# base.net
KiCad netlist of a schematic drawn in EAGLE
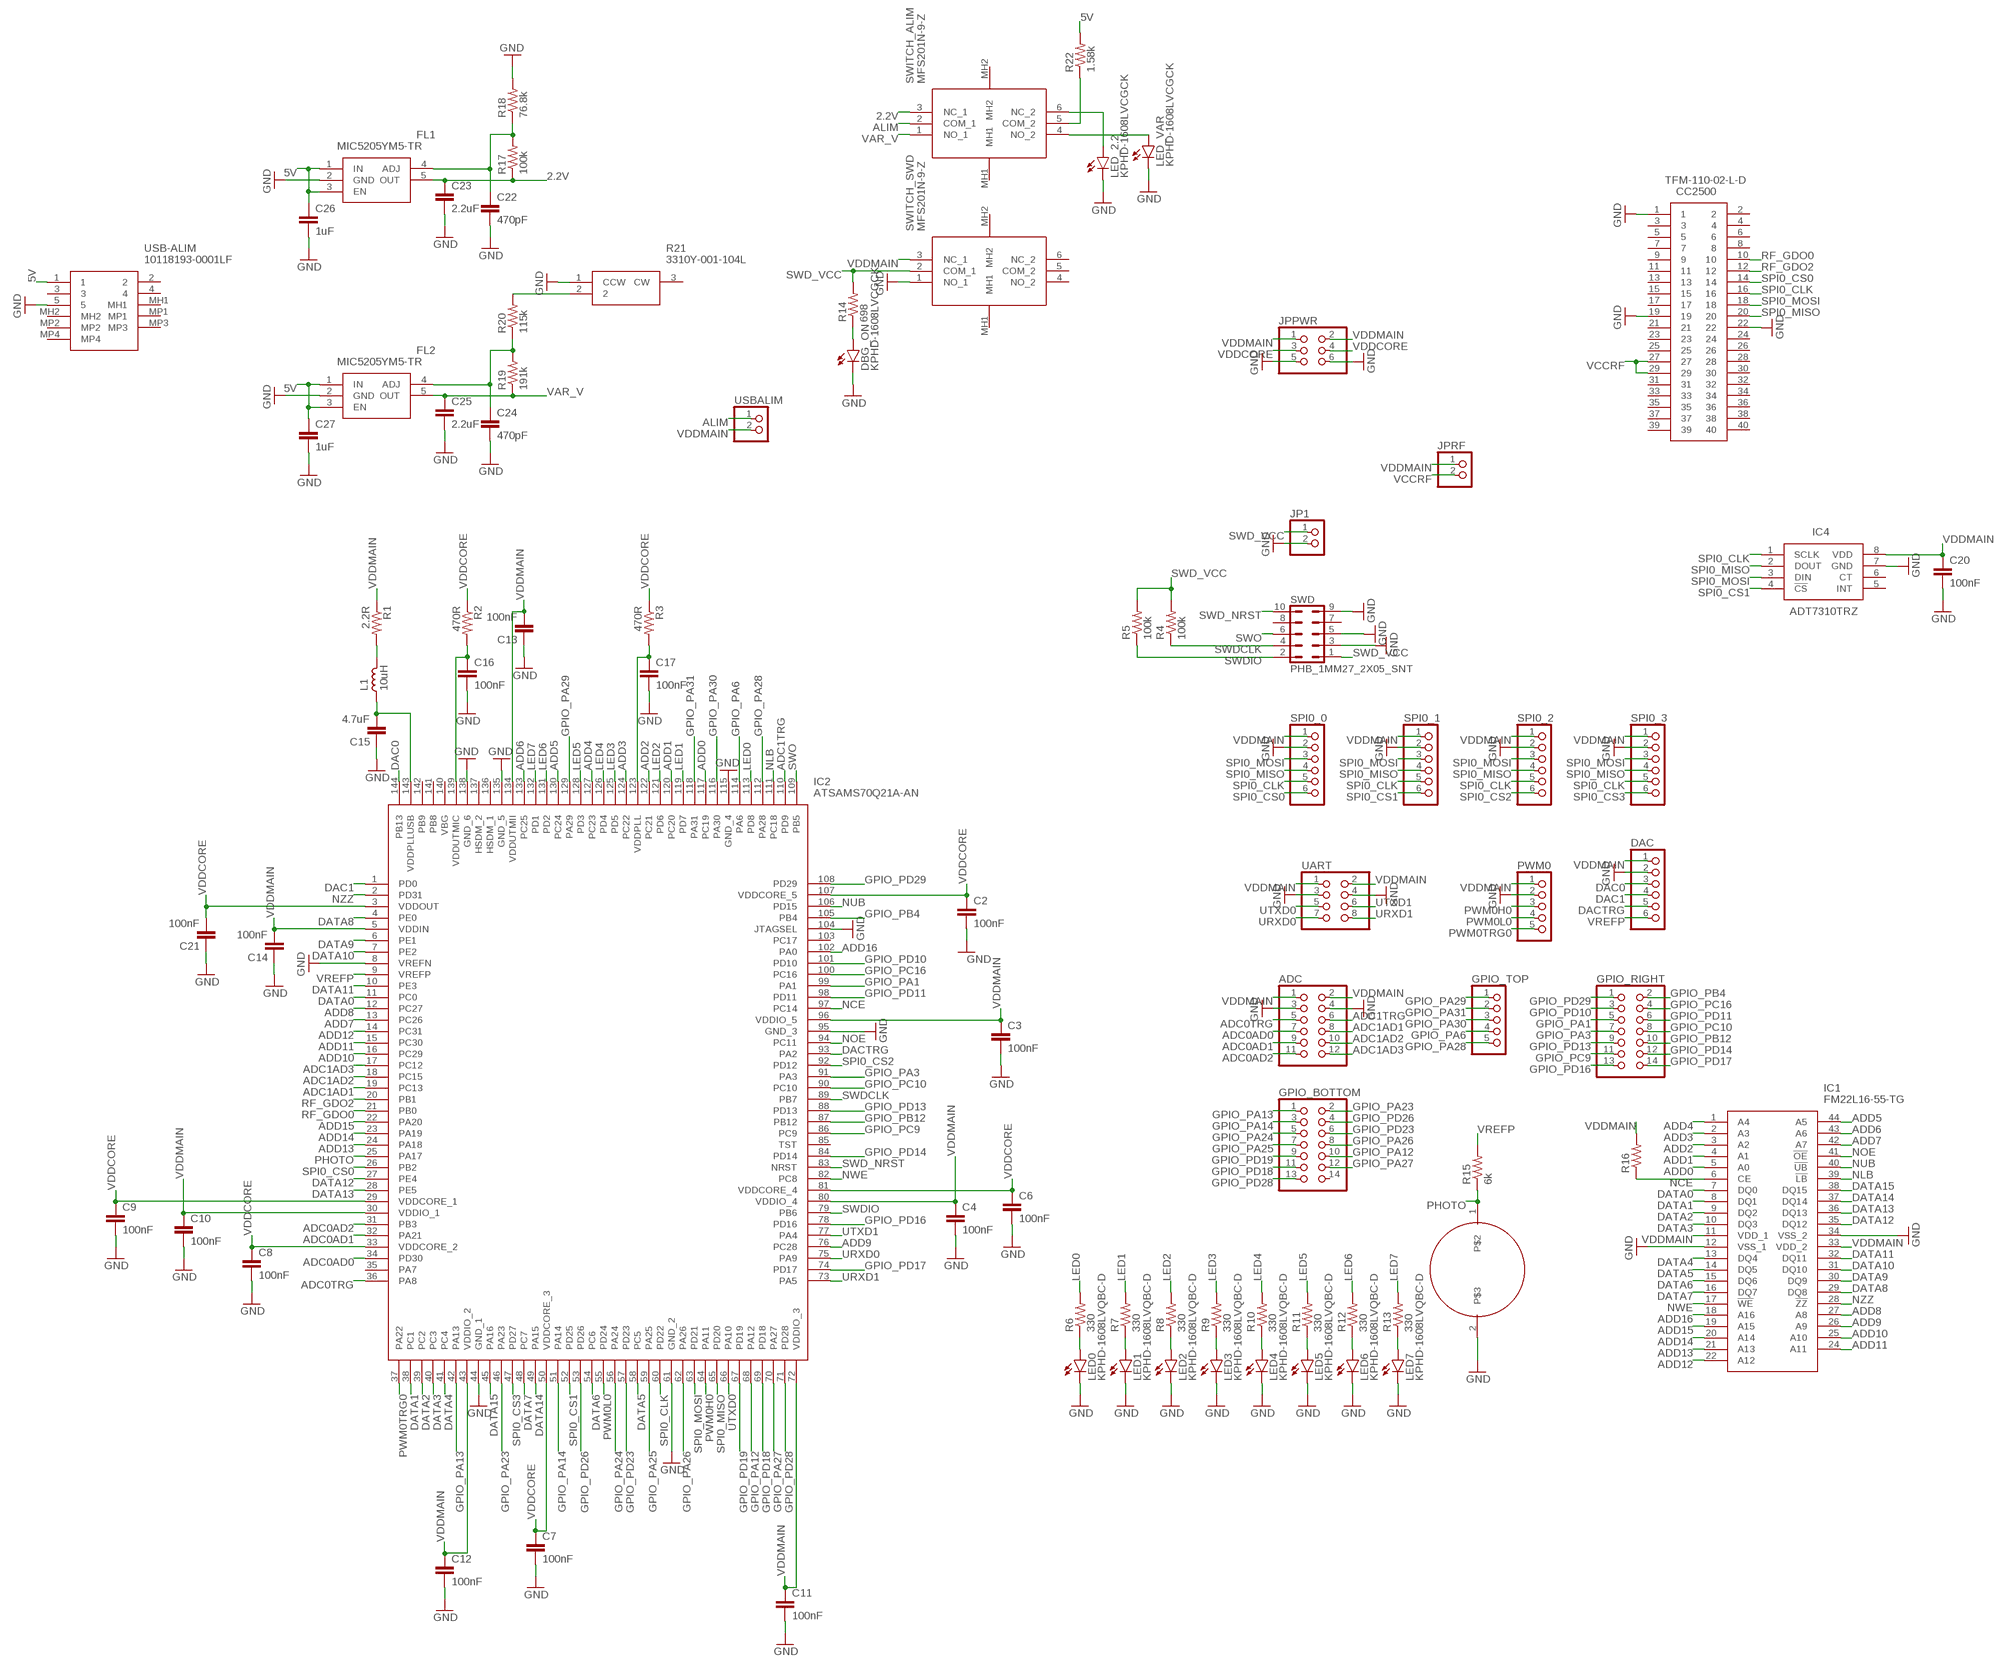
[diagram p0: schematic, sheet 1]

(export (version "E")
  (design (tool "Eeschema 10.0.6"))
  (components
    (comp (ref "ADC")
      (value "PINHD-2X6")
      (footprint "eagle-import:2X06")
      (libsource (lib "eagle-import") (part "PINHD-2X6"))
    )
    (comp (ref "C2")
      (value "100nF")
      (footprint "eagle-import:C0603")
      (libsource (lib "eagle-import") (part "C-EUC0603"))
    )
    (comp (ref "C3")
      (value "100nF")
      (footprint "eagle-import:C0603")
      (libsource (lib "eagle-import") (part "C-EUC0603"))
    )
    (comp (ref "C4")
      (value "100nF")
      (footprint "eagle-import:C0603")
      (libsource (lib "eagle-import") (part "C-EUC0603"))
    )
    (comp (ref "C6")
      (value "100nF")
      (footprint "eagle-import:C0603")
      (libsource (lib "eagle-import") (part "C-EUC0603"))
    )
    (comp (ref "C7")
      (value "100nF")
      (footprint "eagle-import:C0603")
      (libsource (lib "eagle-import") (part "C-EUC0603"))
    )
    (comp (ref "C8")
      (value "100nF")
      (footprint "eagle-import:C0603")
      (libsource (lib "eagle-import") (part "C-EUC0603"))
    )
    (comp (ref "C9")
      (value "100nF")
      (footprint "eagle-import:C0603")
      (libsource (lib "eagle-import") (part "C-EUC0603"))
    )
    (comp (ref "C10")
      (value "100nF")
      (footprint "eagle-import:C0603")
      (libsource (lib "eagle-import") (part "C-EUC0603"))
    )
    (comp (ref "C11")
      (value "100nF")
      (footprint "eagle-import:C0603")
      (libsource (lib "eagle-import") (part "C-EUC0603"))
    )
    (comp (ref "C12")
      (value "100nF")
      (footprint "eagle-import:C0603")
      (libsource (lib "eagle-import") (part "C-EUC0603"))
    )
    (comp (ref "C13")
      (value "100nF")
      (footprint "eagle-import:C0603")
      (libsource (lib "eagle-import") (part "C-EUC0603"))
    )
    (comp (ref "C14")
      (value "100nF")
      (footprint "eagle-import:C0603")
      (libsource (lib "eagle-import") (part "C-EUC0603"))
    )
    (comp (ref "C15")
      (value "4.7uF")
      (footprint "eagle-import:C0603")
      (libsource (lib "eagle-import") (part "C-EUC0603"))
    )
    (comp (ref "C16")
      (value "100nF")
      (footprint "eagle-import:C0603")
      (libsource (lib "eagle-import") (part "C-EUC0603"))
    )
    (comp (ref "C17")
      (value "100nF")
      (footprint "eagle-import:C0603")
      (libsource (lib "eagle-import") (part "C-EUC0603"))
    )
    (comp (ref "C20")
      (value "100nF")
      (footprint "eagle-import:C0603")
      (libsource (lib "eagle-import") (part "C-EUC0603"))
    )
    (comp (ref "C21")
      (value "100nF")
      (footprint "eagle-import:C0603")
      (libsource (lib "eagle-import") (part "C-EUC0603"))
    )
    (comp (ref "C22")
      (value "470pF")
      (footprint "eagle-import:C0603")
      (libsource (lib "eagle-import") (part "C-EUC0603"))
    )
    (comp (ref "C23")
      (value "2.2uF")
      (footprint "eagle-import:C0603")
      (libsource (lib "eagle-import") (part "C-EUC0603"))
    )
    (comp (ref "C24")
      (value "470pF")
      (footprint "eagle-import:C0603")
      (libsource (lib "eagle-import") (part "C-EUC0603"))
    )
    (comp (ref "C25")
      (value "2.2uF")
      (footprint "eagle-import:C0603")
      (libsource (lib "eagle-import") (part "C-EUC0603"))
    )
    (comp (ref "C26")
      (value "1uF")
      (footprint "eagle-import:C0603")
      (libsource (lib "eagle-import") (part "C-EUC0603"))
    )
    (comp (ref "C27")
      (value "1uF")
      (footprint "eagle-import:C0603")
      (libsource (lib "eagle-import") (part "C-EUC0603"))
    )
    (comp (ref "CC2500")
      (value "TFM-110-02-L-D")
      (footprint "eagle-import:TFM-110-02-L")
      (fields (field (name "MOUSER_PART_NUMBER") "200-TFM11002LD") (field (name "RS_PART_NUMBER") "7655947"))
      (libsource (lib "eagle-import") (part "TFM-110-02-L-D"))
    )
    (comp (ref "DAC")
      (value "PINHD-1X6")
      (footprint "eagle-import:1X06")
      (libsource (lib "eagle-import") (part "PINHD-1X6"))
    )
    (comp (ref "DBG_ON")
      (value "KPHD-1608LVCGCK")
      (footprint "eagle-import:CHIP-LED0603")
      (libsource (lib "eagle-import") (part "LEDCHIP-LED0603"))
    )
    (comp (ref "FL1")
      (value "MIC5205YM5-TR")
      (footprint "eagle-import:SOT95P280X145-5N")
      (fields
        (field (name "MOUSER_PART_NUMBER") "998-MIC5205YM5TR")
        (field (name "RS_PART_NUMBER") "9101449P")
      )
      (libsource (lib "eagle-import") (part "MIC5205YM5-TR"))
    )
    (comp (ref "FL2")
      (value "MIC5205YM5-TR")
      (footprint "eagle-import:SOT95P280X145-5N")
      (fields
        (field (name "MOUSER_PART_NUMBER") "998-MIC5205YM5TR")
        (field (name "RS_PART_NUMBER") "9101449P")
      )
      (libsource (lib "eagle-import") (part "MIC5205YM5-TR"))
    )
    (comp (ref "GPIO_BOTTOM")
      (value "PINHD-2X7")
      (footprint "eagle-import:2X07")
      (libsource (lib "eagle-import") (part "PINHD-2X7"))
    )
    (comp (ref "GPIO_RIGHT")
      (value "PINHD-2X7")
      (footprint "eagle-import:2X07")
      (libsource (lib "eagle-import") (part "PINHD-2X7"))
    )
    (comp (ref "GPIO_TOP")
      (value "PINHD-1X5")
      (footprint "eagle-import:1X05")
      (libsource (lib "eagle-import") (part "PINHD-1X5"))
    )
    (comp (ref "IC1")
      (value "FM22L16-55-TG")
      (footprint "eagle-import:SOP80P1184X119-44N")
      (fields
        (field (name "MOUSER_PART_NUMBER") "877-FM22L16-55-TG")
        (field (name "RS_PART_NUMBER") "1254206P")
      )
      (libsource (lib "eagle-import") (part "FM22L16-55-TG"))
    )
    (comp (ref "IC2")
      (value "ATSAMS70Q21A-AN")
      (footprint "eagle-import:QFP50P2200X2200X160-144N")
      (fields
        (field (name "MOUSER_PART_NUMBER") "556-ATSAMS70Q21A-AN")
        (field (name "RS_PART_NUMBER") "1773760P")
      )
      (libsource (lib "eagle-import") (part "ATSAMS70Q21A-AN"))
    )
    (comp (ref "IC4")
      (value "ADT7310TRZ")
      (footprint "eagle-import:SOIC127P600X175-8N")
      (fields (field (name "MOUSER_PART_NUMBER") "584-ADT7310TRZ") (field (name "RS_PART_NUMBER") "7969022P"))
      (libsource (lib "eagle-import") (part "ADT7310TRZ"))
    )
    (comp (ref "JP1")
      (value "PINHD-1X2")
      (footprint "eagle-import:1X02")
      (libsource (lib "eagle-import") (part "PINHD-1X2"))
    )
    (comp (ref "JPPWR")
      (value "PINHD-2X3")
      (footprint "eagle-import:2X03")
      (libsource (lib "eagle-import") (part "PINHD-2X3"))
    )
    (comp (ref "JPRF")
      (value "PINHD-1X2")
      (footprint "eagle-import:1X02")
      (libsource (lib "eagle-import") (part "PINHD-1X2"))
    )
    (comp (ref "L1")
      (value "10uH")
      (footprint "eagle-import:L0603")
      (libsource (lib "eagle-import") (part "L_0603"))
    )
    (comp (ref "LED0")
      (value "KPHD-1608LVQBC-D")
      (footprint "eagle-import:CHIP-LED0603")
      (libsource (lib "eagle-import") (part "LEDCHIP-LED0603"))
    )
    (comp (ref "LED1")
      (value "KPHD-1608LVQBC-D")
      (footprint "eagle-import:CHIP-LED0603")
      (libsource (lib "eagle-import") (part "LEDCHIP-LED0603"))
    )
    (comp (ref "LED2")
      (value "KPHD-1608LVQBC-D")
      (footprint "eagle-import:CHIP-LED0603")
      (libsource (lib "eagle-import") (part "LEDCHIP-LED0603"))
    )
    (comp (ref "LED3")
      (value "KPHD-1608LVQBC-D")
      (footprint "eagle-import:CHIP-LED0603")
      (libsource (lib "eagle-import") (part "LEDCHIP-LED0603"))
    )
    (comp (ref "LED4")
      (value "KPHD-1608LVQBC-D")
      (footprint "eagle-import:CHIP-LED0603")
      (libsource (lib "eagle-import") (part "LEDCHIP-LED0603"))
    )
    (comp (ref "LED5")
      (value "KPHD-1608LVQBC-D")
      (footprint "eagle-import:CHIP-LED0603")
      (libsource (lib "eagle-import") (part "LEDCHIP-LED0603"))
    )
    (comp (ref "LED6")
      (value "KPHD-1608LVQBC-D")
      (footprint "eagle-import:CHIP-LED0603")
      (libsource (lib "eagle-import") (part "LEDCHIP-LED0603"))
    )
    (comp (ref "LED7")
      (value "KPHD-1608LVQBC-D")
      (footprint "eagle-import:CHIP-LED0603")
      (libsource (lib "eagle-import") (part "LEDCHIP-LED0603"))
    )
    (comp (ref "LED_2.2")
      (value "KPHD-1608LVCGCK")
      (footprint "eagle-import:CHIP-LED0603")
      (libsource (lib "eagle-import") (part "LEDCHIP-LED0603"))
    )
    (comp (ref "LED_VAR")
      (value "KPHD-1608LVCGCK")
      (footprint "eagle-import:CHIP-LED0603")
      (libsource (lib "eagle-import") (part "LEDCHIP-LED0603"))
    )
    (comp (ref "PWM0")
      (value "PINHD-1X5")
      (footprint "eagle-import:1X05")
      (libsource (lib "eagle-import") (part "PINHD-1X5"))
    )
    (comp (ref "R1")
      (value "2.2R")
      (footprint "eagle-import:R0603")
      (libsource (lib "eagle-import") (part "R-US_R0603"))
    )
    (comp (ref "R2")
      (value "470R")
      (footprint "eagle-import:R0603")
      (libsource (lib "eagle-import") (part "R-US_R0603"))
    )
    (comp (ref "R3")
      (value "470R")
      (footprint "eagle-import:R0603")
      (libsource (lib "eagle-import") (part "R-US_R0603"))
    )
    (comp (ref "R4")
      (value "100k")
      (footprint "eagle-import:R0603")
      (libsource (lib "eagle-import") (part "R-US_R0603"))
    )
    (comp (ref "R5")
      (value "100k")
      (footprint "eagle-import:R0603")
      (libsource (lib "eagle-import") (part "R-US_R0603"))
    )
    (comp (ref "R6")
      (value "330")
      (footprint "eagle-import:R0603")
      (libsource (lib "eagle-import") (part "R-US_R0603"))
    )
    (comp (ref "R7")
      (value "330")
      (footprint "eagle-import:R0603")
      (libsource (lib "eagle-import") (part "R-US_R0603"))
    )
    (comp (ref "R8")
      (value "330")
      (footprint "eagle-import:R0603")
      (libsource (lib "eagle-import") (part "R-US_R0603"))
    )
    (comp (ref "R9")
      (value "330")
      (footprint "eagle-import:R0603")
      (libsource (lib "eagle-import") (part "R-US_R0603"))
    )
    (comp (ref "R10")
      (value "330")
      (footprint "eagle-import:R0603")
      (libsource (lib "eagle-import") (part "R-US_R0603"))
    )
    (comp (ref "R11")
      (value "330")
      (footprint "eagle-import:R0603")
      (libsource (lib "eagle-import") (part "R-US_R0603"))
    )
    (comp (ref "R12")
      (value "330")
      (footprint "eagle-import:R0603")
      (libsource (lib "eagle-import") (part "R-US_R0603"))
    )
    (comp (ref "R13")
      (value "330")
      (footprint "eagle-import:R0603")
      (libsource (lib "eagle-import") (part "R-US_R0603"))
    )
    (comp (ref "R14")
      (value "698")
      (footprint "eagle-import:R0603")
      (libsource (lib "eagle-import") (part "R-US_R0603"))
    )
    (comp (ref "R15")
      (value "6k")
      (footprint "eagle-import:R0603")
      (libsource (lib "eagle-import") (part "R-US_R0603"))
    )
    (comp (ref "R16")
      (value "R-US_R0603")
      (footprint "eagle-import:R0603")
      (libsource (lib "eagle-import") (part "R-US_R0603"))
    )
    (comp (ref "R17")
      (value "100k")
      (footprint "eagle-import:R0603")
      (libsource (lib "eagle-import") (part "R-US_R0603"))
    )
    (comp (ref "R18")
      (value "76.8k")
      (footprint "eagle-import:R0603")
      (libsource (lib "eagle-import") (part "R-US_R0603"))
    )
    (comp (ref "R19")
      (value "191k")
      (footprint "eagle-import:R0603")
      (libsource (lib "eagle-import") (part "R-US_R0603"))
    )
    (comp (ref "R20")
      (value "115k")
      (footprint "eagle-import:R0603")
      (libsource (lib "eagle-import") (part "R-US_R0603"))
    )
    (comp (ref "R21")
      (value "3310Y-001-104L")
      (footprint "eagle-import:3310Y-001")
      (fields
        (field (name "MOUSER_PART_NUMBER") "652-3310Y-001-104L")
        (field (name "RS_PART_NUMBER") "2508317400")
      )
      (libsource (lib "eagle-import") (part "3310Y-001-104L"))
    )
    (comp (ref "R22")
      (value "1.58k")
      (footprint "eagle-import:R0603")
      (libsource (lib "eagle-import") (part "R-US_R0603"))
    )
    (comp (ref "SPI0_0")
      (value "PINHD-1X6")
      (footprint "eagle-import:1X06")
      (libsource (lib "eagle-import") (part "PINHD-1X6"))
    )
    (comp (ref "SPI0_1")
      (value "PINHD-1X6")
      (footprint "eagle-import:1X06")
      (libsource (lib "eagle-import") (part "PINHD-1X6"))
    )
    (comp (ref "SPI0_2")
      (value "PINHD-1X6")
      (footprint "eagle-import:1X06")
      (libsource (lib "eagle-import") (part "PINHD-1X6"))
    )
    (comp (ref "SPI0_3")
      (value "PINHD-1X6")
      (footprint "eagle-import:1X06")
      (libsource (lib "eagle-import") (part "PINHD-1X6"))
    )
    (comp (ref "SWD")
      (value "PHB_1MM27_2X05_SNT")
      (footprint "eagle-import:PHB_1MM27_2X05_SNT")
      (libsource (lib "eagle-import") (part "PHB_1MM27_2X05_SNT"))
    )
    (comp (ref "SWITCH_ALIM")
      (value "MFS201N-9-Z")
      (footprint "eagle-import:MFS201N9Z")
      (libsource (lib "eagle-import") (part "MFS201N-9-Z"))
    )
    (comp (ref "SWITCH_SWD")
      (value "MFS201N-9-Z")
      (footprint "eagle-import:MFS201N9Z")
      (libsource (lib "eagle-import") (part "MFS201N-9-Z"))
    )
    (comp (ref "U$1")
      (value "NSL-4962")
      (footprint "eagle-import:TO-8")
      (libsource (lib "eagle-import") (part "NSL-4962"))
    )
    (comp (ref "UART")
      (value "PINHD-2X4")
      (footprint "eagle-import:2X04")
      (libsource (lib "eagle-import") (part "PINHD-2X4"))
    )
    (comp (ref "USB-ALIM")
      (value "10118193-0001LF")
      (footprint "eagle-import:101181930001LF")
      (fields
        (field (name "MOUSER_PART_NUMBER") "649-10118193-0001LF")
        (field (name "RS_PART_NUMBER") "8632989")
      )
      (libsource (lib "eagle-import") (part "10118193-0001LF"))
    )
    (comp (ref "USBALIM")
      (value "PINHD-1X2")
      (footprint "eagle-import:1X02")
      (libsource (lib "eagle-import") (part "PINHD-1X2"))
    )
  )
  (nets
    (net (code "1") (name "/2.2V") (class "Default")
      (node (ref "C23") (pin "1") (pinfunction "1_1") (pintype "passive"))
      (node (ref "FL1") (pin "5") (pinfunction "OUT_5") (pintype "bidirectional"))
      (node (ref "R17") (pin "1") (pinfunction "1_1") (pintype "passive"))
      (node (ref "SWITCH_ALIM") (pin "3") (pinfunction "NC_1_3") (pintype "bidirectional"))
    )
    (net (code "2") (name "/5V") (class "Default")
      (node (ref "C26") (pin "1") (pinfunction "1_1") (pintype "passive"))
      (node (ref "C27") (pin "1") (pinfunction "1_1") (pintype "passive"))
      (node (ref "FL1") (pin "1") (pinfunction "IN_1") (pintype "bidirectional"))
      (node (ref "FL1") (pin "3") (pinfunction "EN_3") (pintype "bidirectional"))
      (node (ref "FL2") (pin "1") (pinfunction "IN_1") (pintype "bidirectional"))
      (node (ref "FL2") (pin "3") (pinfunction "EN_3") (pintype "bidirectional"))
      (node (ref "R22") (pin "2") (pinfunction "2_2") (pintype "passive"))
      (node (ref "USB-ALIM") (pin "1") (pinfunction "1_1") (pintype "bidirectional"))
    )
    (net (code "3") (name "/ADC0AD0") (class "Default")
      (node (ref "ADC") (pin "7") (pinfunction "7_7") (pintype "passive"))
      (node (ref "IC2") (pin "34") (pinfunction "PD30_34") (pintype "bidirectional"))
    )
    (net (code "4") (name "/ADC0AD1") (class "Default")
      (node (ref "ADC") (pin "9") (pinfunction "9_9") (pintype "passive"))
      (node (ref "IC2") (pin "32") (pinfunction "PA21_32") (pintype "bidirectional"))
    )
    (net (code "5") (name "/ADC0AD2") (class "Default")
      (node (ref "ADC") (pin "11") (pinfunction "11_11") (pintype "passive"))
      (node (ref "IC2") (pin "31") (pinfunction "PB3_31") (pintype "bidirectional"))
    )
    (net (code "6") (name "/ADC0TRG") (class "Default")
      (node (ref "ADC") (pin "5") (pinfunction "5_5") (pintype "passive"))
      (node (ref "IC2") (pin "36") (pinfunction "PA8_36") (pintype "bidirectional"))
    )
    (net (code "7") (name "/ADC1AD1") (class "Default")
      (node (ref "ADC") (pin "8") (pinfunction "8_8") (pintype "passive"))
      (node (ref "IC2") (pin "19") (pinfunction "PC13_19") (pintype "bidirectional"))
    )
    (net (code "8") (name "/ADC1AD2") (class "Default")
      (node (ref "ADC") (pin "10") (pinfunction "10_10") (pintype "passive"))
      (node (ref "IC2") (pin "18") (pinfunction "PC15_18") (pintype "bidirectional"))
    )
    (net (code "9") (name "/ADC1AD3") (class "Default")
      (node (ref "ADC") (pin "12") (pinfunction "12_12") (pintype "passive"))
      (node (ref "IC2") (pin "17") (pinfunction "PC12_17") (pintype "bidirectional"))
    )
    (net (code "10") (name "/ADC1TRG") (class "Default")
      (node (ref "ADC") (pin "6") (pinfunction "6_6") (pintype "passive"))
      (node (ref "IC2") (pin "110") (pinfunction "PD9_110") (pintype "bidirectional"))
    )
    (net (code "11") (name "/ADD0") (class "Default")
      (node (ref "IC1") (pin "5") (pinfunction "A0_5") (pintype "bidirectional"))
      (node (ref "IC2") (pin "117") (pinfunction "PC19_117") (pintype "bidirectional"))
    )
    (net (code "12") (name "/ADD1") (class "Default")
      (node (ref "IC1") (pin "4") (pinfunction "A1_4") (pintype "bidirectional"))
      (node (ref "IC2") (pin "120") (pinfunction "PC20_120") (pintype "bidirectional"))
    )
    (net (code "13") (name "/ADD2") (class "Default")
      (node (ref "IC1") (pin "3") (pinfunction "A2_3") (pintype "bidirectional"))
      (node (ref "IC2") (pin "122") (pinfunction "PC21_122") (pintype "bidirectional"))
    )
    (net (code "14") (name "/ADD3") (class "Default")
      (node (ref "IC1") (pin "2") (pinfunction "A3_2") (pintype "bidirectional"))
      (node (ref "IC2") (pin "124") (pinfunction "PC22_124") (pintype "bidirectional"))
    )
    (net (code "15") (name "/ADD4") (class "Default")
      (node (ref "IC1") (pin "1") (pinfunction "A4_1") (pintype "bidirectional"))
      (node (ref "IC2") (pin "127") (pinfunction "PC23_127") (pintype "bidirectional"))
    )
    (net (code "16") (name "/ADD5") (class "Default")
      (node (ref "IC1") (pin "44") (pinfunction "A5_44") (pintype "bidirectional"))
      (node (ref "IC2") (pin "130") (pinfunction "PC24_130") (pintype "bidirectional"))
    )
    (net (code "17") (name "/ADD6") (class "Default")
      (node (ref "IC1") (pin "43") (pinfunction "A6_43") (pintype "bidirectional"))
      (node (ref "IC2") (pin "133") (pinfunction "PC25_133") (pintype "bidirectional"))
    )
    (net (code "18") (name "/ADD7") (class "Default")
      (node (ref "IC1") (pin "42") (pinfunction "A7_42") (pintype "bidirectional"))
      (node (ref "IC2") (pin "13") (pinfunction "PC26_13") (pintype "bidirectional"))
    )
    (net (code "19") (name "/ADD8") (class "Default")
      (node (ref "IC1") (pin "27") (pinfunction "A8_27") (pintype "bidirectional"))
      (node (ref "IC2") (pin "12") (pinfunction "PC27_12") (pintype "bidirectional"))
    )
    (net (code "20") (name "/ADD9") (class "Default")
      (node (ref "IC1") (pin "26") (pinfunction "A9_26") (pintype "bidirectional"))
      (node (ref "IC2") (pin "76") (pinfunction "PC28_76") (pintype "bidirectional"))
    )
    (net (code "21") (name "/ADD10") (class "Default")
      (node (ref "IC1") (pin "25") (pinfunction "A10_25") (pintype "bidirectional"))
      (node (ref "IC2") (pin "16") (pinfunction "PC29_16") (pintype "bidirectional"))
    )
    (net (code "22") (name "/ADD11") (class "Default")
      (node (ref "IC1") (pin "24") (pinfunction "A11_24") (pintype "bidirectional"))
      (node (ref "IC2") (pin "15") (pinfunction "PC30_15") (pintype "bidirectional"))
    )
    (net (code "23") (name "/ADD12") (class "Default")
      (node (ref "IC1") (pin "22") (pinfunction "A12_22") (pintype "bidirectional"))
      (node (ref "IC2") (pin "14") (pinfunction "PC31_14") (pintype "bidirectional"))
    )
    (net (code "24") (name "/ADD13") (class "Default")
      (node (ref "IC1") (pin "21") (pinfunction "A13_21") (pintype "bidirectional"))
      (node (ref "IC2") (pin "24") (pinfunction "PA18_24") (pintype "bidirectional"))
    )
    (net (code "25") (name "/ADD14") (class "Default")
      (node (ref "IC1") (pin "20") (pinfunction "A14_20") (pintype "bidirectional"))
      (node (ref "IC2") (pin "23") (pinfunction "PA19_23") (pintype "bidirectional"))
    )
    (net (code "26") (name "/ADD15") (class "Default")
      (node (ref "IC1") (pin "19") (pinfunction "A15_19") (pintype "bidirectional"))
      (node (ref "IC2") (pin "22") (pinfunction "PA20_22") (pintype "bidirectional"))
    )
    (net (code "27") (name "/ADD16") (class "Default")
      (node (ref "IC1") (pin "18") (pinfunction "A16_18") (pintype "bidirectional"))
      (node (ref "IC2") (pin "102") (pinfunction "PA0_102") (pintype "bidirectional"))
    )
    (net (code "28") (name "/ALIM") (class "Default")
      (node (ref "SWITCH_ALIM") (pin "2") (pinfunction "COM_1_2") (pintype "bidirectional"))
      (node (ref "USBALIM") (pin "1") (pinfunction "1_1") (pintype "passive"))
    )
    (net (code "29") (name "/DAC0") (class "Default")
      (node (ref "DAC") (pin "3") (pinfunction "3_3") (pintype "passive"))
      (node (ref "IC2") (pin "144") (pinfunction "PB13_144") (pintype "bidirectional"))
    )
    (net (code "30") (name "/DAC1") (class "Default")
      (node (ref "DAC") (pin "4") (pinfunction "4_4") (pintype "passive"))
      (node (ref "IC2") (pin "1") (pinfunction "PD0_1") (pintype "bidirectional"))
    )
    (net (code "31") (name "/DACTRG") (class "Default")
      (node (ref "DAC") (pin "5") (pinfunction "5_5") (pintype "passive"))
      (node (ref "IC2") (pin "93") (pinfunction "PA2_93") (pintype "bidirectional"))
    )
    (net (code "32") (name "/DATA0") (class "Default")
      (node (ref "IC1") (pin "7") (pinfunction "DQ0_7") (pintype "bidirectional"))
      (node (ref "IC2") (pin "11") (pinfunction "PC0_11") (pintype "bidirectional"))
    )
    (net (code "33") (name "/DATA1") (class "Default")
      (node (ref "IC1") (pin "8") (pinfunction "DQ1_8") (pintype "bidirectional"))
      (node (ref "IC2") (pin "38") (pinfunction "PC1_38") (pintype "bidirectional"))
    )
    (net (code "34") (name "/DATA2") (class "Default")
      (node (ref "IC1") (pin "9") (pinfunction "DQ2_9") (pintype "bidirectional"))
      (node (ref "IC2") (pin "39") (pinfunction "PC2_39") (pintype "bidirectional"))
    )
    (net (code "35") (name "/DATA3") (class "Default")
      (node (ref "IC1") (pin "10") (pinfunction "DQ3_10") (pintype "bidirectional"))
      (node (ref "IC2") (pin "40") (pinfunction "PC3_40") (pintype "bidirectional"))
    )
    (net (code "36") (name "/DATA4") (class "Default")
      (node (ref "IC1") (pin "13") (pinfunction "DQ4_13") (pintype "bidirectional"))
      (node (ref "IC2") (pin "41") (pinfunction "PC4_41") (pintype "bidirectional"))
    )
    (net (code "37") (name "/DATA5") (class "Default")
      (node (ref "IC1") (pin "14") (pinfunction "DQ5_14") (pintype "bidirectional"))
      (node (ref "IC2") (pin "58") (pinfunction "PC5_58") (pintype "bidirectional"))
    )
    (net (code "38") (name "/DATA6") (class "Default")
      (node (ref "IC1") (pin "15") (pinfunction "DQ6_15") (pintype "bidirectional"))
      (node (ref "IC2") (pin "54") (pinfunction "PC6_54") (pintype "bidirectional"))
    )
    (net (code "39") (name "/DATA7") (class "Default")
      (node (ref "IC1") (pin "16") (pinfunction "DQ7_16") (pintype "bidirectional"))
      (node (ref "IC2") (pin "48") (pinfunction "PC7_48") (pintype "bidirectional"))
    )
    (net (code "40") (name "/DATA8") (class "Default")
      (node (ref "IC1") (pin "29") (pinfunction "DQ8_29") (pintype "bidirectional"))
      (node (ref "IC2") (pin "4") (pinfunction "PE0_4") (pintype "bidirectional"))
    )
    (net (code "41") (name "/DATA9") (class "Default")
      (node (ref "IC1") (pin "30") (pinfunction "DQ9_30") (pintype "bidirectional"))
      (node (ref "IC2") (pin "6") (pinfunction "PE1_6") (pintype "bidirectional"))
    )
    (net (code "42") (name "/DATA10") (class "Default")
      (node (ref "IC1") (pin "31") (pinfunction "DQ10_31") (pintype "bidirectional"))
      (node (ref "IC2") (pin "7") (pinfunction "PE2_7") (pintype "bidirectional"))
    )
    (net (code "43") (name "/DATA11") (class "Default")
      (node (ref "IC1") (pin "32") (pinfunction "DQ11_32") (pintype "bidirectional"))
      (node (ref "IC2") (pin "10") (pinfunction "PE3_10") (pintype "bidirectional"))
    )
    (net (code "44") (name "/DATA12") (class "Default")
      (node (ref "IC1") (pin "35") (pinfunction "DQ12_35") (pintype "bidirectional"))
      (node (ref "IC2") (pin "27") (pinfunction "PE4_27") (pintype "bidirectional"))
    )
    (net (code "45") (name "/DATA13") (class "Default")
      (node (ref "IC1") (pin "36") (pinfunction "DQ13_36") (pintype "bidirectional"))
      (node (ref "IC2") (pin "28") (pinfunction "PE5_28") (pintype "bidirectional"))
    )
    (net (code "46") (name "/DATA14") (class "Default")
      (node (ref "IC1") (pin "37") (pinfunction "DQ14_37") (pintype "bidirectional"))
      (node (ref "IC2") (pin "49") (pinfunction "PA15_49") (pintype "bidirectional"))
    )
    (net (code "47") (name "/DATA15") (class "Default")
      (node (ref "IC1") (pin "38") (pinfunction "DQ15_38") (pintype "bidirectional"))
      (node (ref "IC2") (pin "45") (pinfunction "PA16_45") (pintype "bidirectional"))
    )
    (net (code "48") (name "/GPIO_PA1") (class "Default")
      (node (ref "GPIO_RIGHT") (pin "5") (pinfunction "5_5") (pintype "passive"))
      (node (ref "IC2") (pin "99") (pinfunction "PA1_99") (pintype "bidirectional"))
    )
    (net (code "49") (name "/GPIO_PA3") (class "Default")
      (node (ref "GPIO_RIGHT") (pin "7") (pinfunction "7_7") (pintype "passive"))
      (node (ref "IC2") (pin "91") (pinfunction "PA3_91") (pintype "bidirectional"))
    )
    (net (code "50") (name "/GPIO_PA6") (class "Default")
      (node (ref "GPIO_TOP") (pin "4") (pinfunction "4_4") (pintype "passive"))
      (node (ref "IC2") (pin "114") (pinfunction "PA6_114") (pintype "bidirectional"))
    )
    (net (code "51") (name "/GPIO_PA12") (class "Default")
      (node (ref "GPIO_BOTTOM") (pin "10") (pinfunction "10_10") (pintype "passive"))
      (node (ref "IC2") (pin "68") (pinfunction "PA12_68") (pintype "bidirectional"))
    )
    (net (code "52") (name "/GPIO_PA13") (class "Default")
      (node (ref "GPIO_BOTTOM") (pin "1") (pinfunction "1_1") (pintype "passive"))
      (node (ref "IC2") (pin "42") (pinfunction "PA13_42") (pintype "bidirectional"))
    )
    (net (code "53") (name "/GPIO_PA14") (class "Default")
      (node (ref "GPIO_BOTTOM") (pin "3") (pinfunction "3_3") (pintype "passive"))
      (node (ref "IC2") (pin "51") (pinfunction "PA14_51") (pintype "bidirectional"))
    )
    (net (code "54") (name "/GPIO_PA23") (class "Default")
      (node (ref "GPIO_BOTTOM") (pin "2") (pinfunction "2_2") (pintype "passive"))
      (node (ref "IC2") (pin "46") (pinfunction "PA23_46") (pintype "bidirectional"))
    )
    (net (code "55") (name "/GPIO_PA24") (class "Default")
      (node (ref "GPIO_BOTTOM") (pin "5") (pinfunction "5_5") (pintype "passive"))
      (node (ref "IC2") (pin "56") (pinfunction "PA24_56") (pintype "bidirectional"))
    )
    (net (code "56") (name "/GPIO_PA25") (class "Default")
      (node (ref "GPIO_BOTTOM") (pin "7") (pinfunction "7_7") (pintype "passive"))
      (node (ref "IC2") (pin "59") (pinfunction "PA25_59") (pintype "bidirectional"))
    )
    (net (code "57") (name "/GPIO_PA26") (class "Default")
      (node (ref "GPIO_BOTTOM") (pin "8") (pinfunction "8_8") (pintype "passive"))
      (node (ref "IC2") (pin "62") (pinfunction "PA26_62") (pintype "bidirectional"))
    )
    (net (code "58") (name "/GPIO_PA27") (class "Default")
      (node (ref "GPIO_BOTTOM") (pin "12") (pinfunction "12_12") (pintype "passive"))
      (node (ref "IC2") (pin "70") (pinfunction "PA27_70") (pintype "bidirectional"))
    )
    (net (code "59") (name "/GPIO_PA28") (class "Default")
      (node (ref "GPIO_TOP") (pin "5") (pinfunction "5_5") (pintype "passive"))
      (node (ref "IC2") (pin "112") (pinfunction "PA28_112") (pintype "bidirectional"))
    )
    (net (code "60") (name "/GPIO_PA29") (class "Default")
      (node (ref "GPIO_TOP") (pin "1") (pinfunction "1_1") (pintype "passive"))
      (node (ref "IC2") (pin "129") (pinfunction "PA29_129") (pintype "bidirectional"))
    )
    (net (code "61") (name "/GPIO_PA30") (class "Default")
      (node (ref "GPIO_TOP") (pin "3") (pinfunction "3_3") (pintype "passive"))
      (node (ref "IC2") (pin "116") (pinfunction "PA30_116") (pintype "bidirectional"))
    )
    (net (code "62") (name "/GPIO_PA31") (class "Default")
      (node (ref "GPIO_TOP") (pin "2") (pinfunction "2_2") (pintype "passive"))
      (node (ref "IC2") (pin "118") (pinfunction "PA31_118") (pintype "bidirectional"))
    )
    (net (code "63") (name "/GPIO_PB4") (class "Default")
      (node (ref "GPIO_RIGHT") (pin "2") (pinfunction "2_2") (pintype "passive"))
      (node (ref "IC2") (pin "105") (pinfunction "PB4_105") (pintype "bidirectional"))
    )
    (net (code "64") (name "/GPIO_PB12") (class "Default")
      (node (ref "GPIO_RIGHT") (pin "10") (pinfunction "10_10") (pintype "passive"))
      (node (ref "IC2") (pin "87") (pinfunction "PB12_87") (pintype "bidirectional"))
    )
    (net (code "65") (name "/GPIO_PC9") (class "Default")
      (node (ref "GPIO_RIGHT") (pin "11") (pinfunction "11_11") (pintype "passive"))
      (node (ref "IC2") (pin "86") (pinfunction "PC9_86") (pintype "bidirectional"))
    )
    (net (code "66") (name "/GPIO_PC10") (class "Default")
      (node (ref "GPIO_RIGHT") (pin "8") (pinfunction "8_8") (pintype "passive"))
      (node (ref "IC2") (pin "90") (pinfunction "PC10_90") (pintype "bidirectional"))
    )
    (net (code "67") (name "/GPIO_PC16") (class "Default")
      (node (ref "GPIO_RIGHT") (pin "4") (pinfunction "4_4") (pintype "passive"))
      (node (ref "IC2") (pin "100") (pinfunction "PC16_100") (pintype "bidirectional"))
    )
    (net (code "68") (name "/GPIO_PD10") (class "Default")
      (node (ref "GPIO_RIGHT") (pin "3") (pinfunction "3_3") (pintype "passive"))
      (node (ref "IC2") (pin "101") (pinfunction "PD10_101") (pintype "bidirectional"))
    )
    (net (code "69") (name "/GPIO_PD11") (class "Default")
      (node (ref "GPIO_RIGHT") (pin "6") (pinfunction "6_6") (pintype "passive"))
      (node (ref "IC2") (pin "98") (pinfunction "PD11_98") (pintype "bidirectional"))
    )
    (net (code "70") (name "/GPIO_PD13") (class "Default")
      (node (ref "GPIO_RIGHT") (pin "9") (pinfunction "9_9") (pintype "passive"))
      (node (ref "IC2") (pin "88") (pinfunction "PD13_88") (pintype "bidirectional"))
    )
    (net (code "71") (name "/GPIO_PD14") (class "Default")
      (node (ref "GPIO_RIGHT") (pin "12") (pinfunction "12_12") (pintype "passive"))
      (node (ref "IC2") (pin "84") (pinfunction "PD14_84") (pintype "bidirectional"))
    )
    (net (code "72") (name "/GPIO_PD16") (class "Default")
      (node (ref "GPIO_RIGHT") (pin "13") (pinfunction "13_13") (pintype "passive"))
      (node (ref "IC2") (pin "78") (pinfunction "PD16_78") (pintype "bidirectional"))
    )
    (net (code "73") (name "/GPIO_PD17") (class "Default")
      (node (ref "GPIO_RIGHT") (pin "14") (pinfunction "14_14") (pintype "passive"))
      (node (ref "IC2") (pin "74") (pinfunction "PD17_74") (pintype "bidirectional"))
    )
    (net (code "74") (name "/GPIO_PD18") (class "Default")
      (node (ref "GPIO_BOTTOM") (pin "11") (pinfunction "11_11") (pintype "passive"))
      (node (ref "IC2") (pin "69") (pinfunction "PD18_69") (pintype "bidirectional"))
    )
    (net (code "75") (name "/GPIO_PD19") (class "Default")
      (node (ref "GPIO_BOTTOM") (pin "9") (pinfunction "9_9") (pintype "passive"))
      (node (ref "IC2") (pin "67") (pinfunction "PD19_67") (pintype "bidirectional"))
    )
    (net (code "76") (name "/GPIO_PD23") (class "Default")
      (node (ref "GPIO_BOTTOM") (pin "6") (pinfunction "6_6") (pintype "passive"))
      (node (ref "IC2") (pin "57") (pinfunction "PD23_57") (pintype "bidirectional"))
    )
    (net (code "77") (name "/GPIO_PD26") (class "Default")
      (node (ref "GPIO_BOTTOM") (pin "4") (pinfunction "4_4") (pintype "passive"))
      (node (ref "IC2") (pin "53") (pinfunction "PD26_53") (pintype "bidirectional"))
    )
    (net (code "78") (name "/GPIO_PD28") (class "Default")
      (node (ref "GPIO_BOTTOM") (pin "13") (pinfunction "13_13") (pintype "passive"))
      (node (ref "IC2") (pin "71") (pinfunction "PD28_71") (pintype "bidirectional"))
    )
    (net (code "79") (name "/GPIO_PD29") (class "Default")
      (node (ref "GPIO_RIGHT") (pin "1") (pinfunction "1_1") (pintype "passive"))
      (node (ref "IC2") (pin "108") (pinfunction "PD29_108") (pintype "bidirectional"))
    )
    (net (code "80") (name "/LED0") (class "Default")
      (node (ref "IC2") (pin "113") (pinfunction "PD8_113") (pintype "bidirectional"))
      (node (ref "R6") (pin "2") (pinfunction "2_2") (pintype "passive"))
    )
    (net (code "81") (name "/LED1") (class "Default")
      (node (ref "IC2") (pin "119") (pinfunction "PD7_119") (pintype "bidirectional"))
      (node (ref "R7") (pin "2") (pinfunction "2_2") (pintype "passive"))
    )
    (net (code "82") (name "/LED2") (class "Default")
      (node (ref "IC2") (pin "121") (pinfunction "PD6_121") (pintype "bidirectional"))
      (node (ref "R8") (pin "2") (pinfunction "2_2") (pintype "passive"))
    )
    (net (code "83") (name "/LED3") (class "Default")
      (node (ref "IC2") (pin "125") (pinfunction "PD5_125") (pintype "bidirectional"))
      (node (ref "R9") (pin "2") (pinfunction "2_2") (pintype "passive"))
    )
    (net (code "84") (name "/LED4") (class "Default")
      (node (ref "IC2") (pin "126") (pinfunction "PD4_126") (pintype "bidirectional"))
      (node (ref "R10") (pin "2") (pinfunction "2_2") (pintype "passive"))
    )
    (net (code "85") (name "/LED5") (class "Default")
      (node (ref "IC2") (pin "128") (pinfunction "PD3_128") (pintype "bidirectional"))
      (node (ref "R11") (pin "2") (pinfunction "2_2") (pintype "passive"))
    )
    (net (code "86") (name "/LED6") (class "Default")
      (node (ref "IC2") (pin "131") (pinfunction "PD2_131") (pintype "bidirectional"))
      (node (ref "R12") (pin "2") (pinfunction "2_2") (pintype "passive"))
    )
    (net (code "87") (name "/LED7") (class "Default")
      (node (ref "IC2") (pin "132") (pinfunction "PD1_132") (pintype "bidirectional"))
      (node (ref "R13") (pin "2") (pinfunction "2_2") (pintype "passive"))
    )
    (net (code "88") (name "/NCE") (class "Default")
      (node (ref "IC1") (pin "6") (pinfunction "CE_6") (pintype "bidirectional"))
      (node (ref "IC2") (pin "97") (pinfunction "PC14_97") (pintype "bidirectional"))
      (node (ref "R16") (pin "1") (pinfunction "1_1") (pintype "passive"))
    )
    (net (code "89") (name "/NLB") (class "Default")
      (node (ref "IC1") (pin "39") (pinfunction "~{LB}_39") (pintype "bidirectional"))
      (node (ref "IC2") (pin "111") (pinfunction "PC18_111") (pintype "bidirectional"))
    )
    (net (code "90") (name "/NOE") (class "Default")
      (node (ref "IC1") (pin "41") (pinfunction "~{OE}_41") (pintype "bidirectional"))
      (node (ref "IC2") (pin "94") (pinfunction "PC11_94") (pintype "bidirectional"))
    )
    (net (code "91") (name "/NUB") (class "Default")
      (node (ref "IC1") (pin "40") (pinfunction "~{UB}_40") (pintype "bidirectional"))
      (node (ref "IC2") (pin "106") (pinfunction "PD15_106") (pintype "bidirectional"))
    )
    (net (code "92") (name "/NWE") (class "Default")
      (node (ref "IC1") (pin "17") (pinfunction "~{WE}_17") (pintype "bidirectional"))
      (node (ref "IC2") (pin "82") (pinfunction "PC8_82") (pintype "bidirectional"))
    )
    (net (code "93") (name "/NZZ") (class "Default")
      (node (ref "IC1") (pin "28") (pinfunction "~{ZZ}_28") (pintype "bidirectional"))
      (node (ref "IC2") (pin "2") (pinfunction "PD31_2") (pintype "bidirectional"))
    )
    (net (code "94") (name "/PHOTO") (class "Default")
      (node (ref "IC2") (pin "25") (pinfunction "PA17_25") (pintype "bidirectional"))
      (node (ref "R15") (pin "1") (pinfunction "1_1") (pintype "passive"))
      (node (ref "U$1") (pin "1") (pinfunction "P$2_1") (pintype "bidirectional"))
    )
    (net (code "95") (name "/PWM0H0") (class "Default")
      (node (ref "IC2") (pin "64") (pinfunction "PA11_64") (pintype "bidirectional"))
      (node (ref "PWM0") (pin "3") (pinfunction "3_3") (pintype "passive"))
    )
    (net (code "96") (name "/PWM0L0") (class "Default")
      (node (ref "IC2") (pin "55") (pinfunction "PD24_55") (pintype "bidirectional"))
      (node (ref "PWM0") (pin "4") (pinfunction "4_4") (pintype "passive"))
    )
    (net (code "97") (name "/PWM0TRG0") (class "Default")
      (node (ref "IC2") (pin "37") (pinfunction "PA22_37") (pintype "bidirectional"))
      (node (ref "PWM0") (pin "5") (pinfunction "5_5") (pintype "passive"))
    )
    (net (code "98") (name "/RF_GDO0") (class "Default")
      (node (ref "CC2500") (pin "10") (pinfunction "10_10") (pintype "bidirectional"))
      (node (ref "IC2") (pin "21") (pinfunction "PB0_21") (pintype "bidirectional"))
    )
    (net (code "99") (name "/RF_GDO2") (class "Default")
      (node (ref "CC2500") (pin "12") (pinfunction "12_12") (pintype "bidirectional"))
      (node (ref "IC2") (pin "20") (pinfunction "PB1_20") (pintype "bidirectional"))
    )
    (net (code "100") (name "/SPI0_CLK") (class "Default")
      (node (ref "CC2500") (pin "16") (pinfunction "16_16") (pintype "bidirectional"))
      (node (ref "IC2") (pin "60") (pinfunction "PD22_60") (pintype "bidirectional"))
      (node (ref "IC4") (pin "1") (pinfunction "SCLK_1") (pintype "input"))
      (node (ref "SPI0_0") (pin "5") (pinfunction "5_5") (pintype "passive"))
      (node (ref "SPI0_1") (pin "5") (pinfunction "5_5") (pintype "passive"))
      (node (ref "SPI0_2") (pin "5") (pinfunction "5_5") (pintype "passive"))
      (node (ref "SPI0_3") (pin "5") (pinfunction "5_5") (pintype "passive"))
    )
    (net (code "101") (name "/SPI0_CS0") (class "Default")
      (node (ref "CC2500") (pin "14") (pinfunction "14_14") (pintype "bidirectional"))
      (node (ref "IC2") (pin "26") (pinfunction "PB2_26") (pintype "bidirectional"))
      (node (ref "SPI0_0") (pin "6") (pinfunction "6_6") (pintype "passive"))
    )
    (net (code "102") (name "/SPI0_CS1") (class "Default")
      (node (ref "IC2") (pin "52") (pinfunction "PD25_52") (pintype "bidirectional"))
      (node (ref "IC4") (pin "4") (pinfunction "~{CS}_4") (pintype "input"))
      (node (ref "SPI0_1") (pin "6") (pinfunction "6_6") (pintype "passive"))
    )
    (net (code "103") (name "/SPI0_CS2") (class "Default")
      (node (ref "IC2") (pin "92") (pinfunction "PD12_92") (pintype "bidirectional"))
      (node (ref "SPI0_2") (pin "6") (pinfunction "6_6") (pintype "passive"))
    )
    (net (code "104") (name "/SPI0_CS3") (class "Default")
      (node (ref "IC2") (pin "47") (pinfunction "PD27_47") (pintype "bidirectional"))
      (node (ref "SPI0_3") (pin "6") (pinfunction "6_6") (pintype "passive"))
    )
    (net (code "105") (name "/SPI0_MISO") (class "Default")
      (node (ref "CC2500") (pin "20") (pinfunction "20_20") (pintype "bidirectional"))
      (node (ref "IC2") (pin "65") (pinfunction "PD20_65") (pintype "bidirectional"))
      (node (ref "IC4") (pin "2") (pinfunction "DOUT_2") (pintype "output"))
      (node (ref "SPI0_0") (pin "4") (pinfunction "4_4") (pintype "passive"))
      (node (ref "SPI0_1") (pin "4") (pinfunction "4_4") (pintype "passive"))
      (node (ref "SPI0_2") (pin "4") (pinfunction "4_4") (pintype "passive"))
      (node (ref "SPI0_3") (pin "4") (pinfunction "4_4") (pintype "passive"))
    )
    (net (code "106") (name "/SPI0_MOSI") (class "Default")
      (node (ref "CC2500") (pin "18") (pinfunction "18_18") (pintype "bidirectional"))
      (node (ref "IC2") (pin "63") (pinfunction "PD21_63") (pintype "bidirectional"))
      (node (ref "IC4") (pin "3") (pinfunction "DIN_3") (pintype "input"))
      (node (ref "SPI0_0") (pin "3") (pinfunction "3_3") (pintype "passive"))
      (node (ref "SPI0_1") (pin "3") (pinfunction "3_3") (pintype "passive"))
      (node (ref "SPI0_2") (pin "3") (pinfunction "3_3") (pintype "passive"))
      (node (ref "SPI0_3") (pin "3") (pinfunction "3_3") (pintype "passive"))
    )
    (net (code "107") (name "/SWDCLK") (class "Default")
      (node (ref "IC2") (pin "89") (pinfunction "PB7_89") (pintype "bidirectional"))
      (node (ref "R4") (pin "1") (pinfunction "1_1") (pintype "passive"))
      (node (ref "SWD") (pin "4") (pinfunction "4_4") (pintype "passive"))
    )
    (net (code "108") (name "/SWDIO") (class "Default")
      (node (ref "IC2") (pin "79") (pinfunction "PB6_79") (pintype "bidirectional"))
      (node (ref "R5") (pin "1") (pinfunction "1_1") (pintype "passive"))
      (node (ref "SWD") (pin "2") (pinfunction "2_2") (pintype "passive"))
    )
    (net (code "109") (name "/SWD_NRST") (class "Default")
      (node (ref "IC2") (pin "83") (pinfunction "NRST_83") (pintype "bidirectional"))
      (node (ref "SWD") (pin "10") (pinfunction "10_10") (pintype "passive"))
    )
    (net (code "110") (name "/SWD_VCC") (class "Default")
      (node (ref "JP1") (pin "1") (pinfunction "1_1") (pintype "passive"))
      (node (ref "R14") (pin "2") (pinfunction "2_2") (pintype "passive"))
      (node (ref "R4") (pin "2") (pinfunction "2_2") (pintype "passive"))
      (node (ref "R5") (pin "2") (pinfunction "2_2") (pintype "passive"))
      (node (ref "SWD") (pin "1") (pinfunction "1_1") (pintype "passive"))
      (node (ref "SWITCH_SWD") (pin "2") (pinfunction "COM_1_2") (pintype "bidirectional"))
    )
    (net (code "111") (name "/SWO") (class "Default")
      (node (ref "IC2") (pin "109") (pinfunction "PB5_109") (pintype "bidirectional"))
      (node (ref "SWD") (pin "6") (pinfunction "6_6") (pintype "passive"))
    )
    (net (code "112") (name "/URXD0") (class "Default")
      (node (ref "IC2") (pin "75") (pinfunction "PA9_75") (pintype "bidirectional"))
      (node (ref "UART") (pin "7") (pinfunction "7_7") (pintype "passive"))
    )
    (net (code "113") (name "/URXD1") (class "Default")
      (node (ref "IC2") (pin "73") (pinfunction "PA5_73") (pintype "bidirectional"))
      (node (ref "UART") (pin "8") (pinfunction "8_8") (pintype "passive"))
    )
    (net (code "114") (name "/UTXD0") (class "Default")
      (node (ref "IC2") (pin "66") (pinfunction "PA10_66") (pintype "bidirectional"))
      (node (ref "UART") (pin "5") (pinfunction "5_5") (pintype "passive"))
    )
    (net (code "115") (name "/UTXD1") (class "Default")
      (node (ref "IC2") (pin "77") (pinfunction "PA4_77") (pintype "bidirectional"))
      (node (ref "UART") (pin "6") (pinfunction "6_6") (pintype "passive"))
    )
    (net (code "116") (name "/VAR_V") (class "Default")
      (node (ref "C25") (pin "1") (pinfunction "1_1") (pintype "passive"))
      (node (ref "FL2") (pin "5") (pinfunction "OUT_5") (pintype "bidirectional"))
      (node (ref "R19") (pin "1") (pinfunction "1_1") (pintype "passive"))
      (node (ref "SWITCH_ALIM") (pin "1") (pinfunction "NO_1_1") (pintype "bidirectional"))
    )
    (net (code "117") (name "/VCCRF") (class "Default")
      (node (ref "CC2500") (pin "27") (pinfunction "27_27") (pintype "bidirectional"))
      (node (ref "CC2500") (pin "29") (pinfunction "29_29") (pintype "bidirectional"))
      (node (ref "JPRF") (pin "2") (pinfunction "2_2") (pintype "passive"))
    )
    (net (code "118") (name "/VDDCORE") (class "Default")
      (node (ref "C2") (pin "1") (pinfunction "1_1") (pintype "passive"))
      (node (ref "C21") (pin "2") (pinfunction "2_2") (pintype "passive"))
      (node (ref "C6") (pin "1") (pinfunction "1_1") (pintype "passive"))
      (node (ref "C7") (pin "1") (pinfunction "1_1") (pintype "passive"))
      (node (ref "C8") (pin "1") (pinfunction "1_1") (pintype "passive"))
      (node (ref "C9") (pin "1") (pinfunction "1_1") (pintype "passive"))
      (node (ref "IC2") (pin "107") (pinfunction "VDDCORE_5_107") (pintype "power_in"))
      (node (ref "IC2") (pin "29") (pinfunction "VDDCORE_1_29") (pintype "power_in"))
      (node (ref "IC2") (pin "3") (pinfunction "VDDOUT_3") (pintype "power_in"))
      (node (ref "IC2") (pin "33") (pinfunction "VDDCORE_2_33") (pintype "power_in"))
      (node (ref "IC2") (pin "50") (pinfunction "VDDCORE_3_50") (pintype "power_in"))
      (node (ref "IC2") (pin "81") (pinfunction "VDDCORE_4_81") (pintype "power_in"))
      (node (ref "JPPWR") (pin "3") (pinfunction "3_3") (pintype "passive"))
      (node (ref "JPPWR") (pin "4") (pinfunction "4_4") (pintype "passive"))
      (node (ref "R2") (pin "1") (pinfunction "1_1") (pintype "passive"))
      (node (ref "R3") (pin "1") (pinfunction "1_1") (pintype "passive"))
    )
    (net (code "119") (name "/VDDMAIN") (class "Default")
      (node (ref "ADC") (pin "1") (pinfunction "1_1") (pintype "passive"))
      (node (ref "ADC") (pin "2") (pinfunction "2_2") (pintype "passive"))
      (node (ref "C10") (pin "1") (pinfunction "1_1") (pintype "passive"))
      (node (ref "C11") (pin "1") (pinfunction "1_1") (pintype "passive"))
      (node (ref "C12") (pin "1") (pinfunction "1_1") (pintype "passive"))
      (node (ref "C13") (pin "2") (pinfunction "2_2") (pintype "passive"))
      (node (ref "C14") (pin "2") (pinfunction "2_2") (pintype "passive"))
      (node (ref "C20") (pin "1") (pinfunction "1_1") (pintype "passive"))
      (node (ref "C3") (pin "1") (pinfunction "1_1") (pintype "passive"))
      (node (ref "C4") (pin "1") (pinfunction "1_1") (pintype "passive"))
      (node (ref "DAC") (pin "1") (pinfunction "1_1") (pintype "passive"))
      (node (ref "IC1") (pin "11") (pinfunction "VDD_1_11") (pintype "bidirectional"))
      (node (ref "IC1") (pin "33") (pinfunction "VDD_2_33") (pintype "bidirectional"))
      (node (ref "IC2") (pin "134") (pinfunction "VDDUTMII_134") (pintype "power_in"))
      (node (ref "IC2") (pin "30") (pinfunction "VDDIO_1_30") (pintype "power_in"))
      (node (ref "IC2") (pin "43") (pinfunction "VDDIO_2_43") (pintype "power_in"))
      (node (ref "IC2") (pin "5") (pinfunction "VDDIN_5") (pintype "power_in"))
      (node (ref "IC2") (pin "72") (pinfunction "VDDIO_3_72") (pintype "power_in"))
      (node (ref "IC2") (pin "80") (pinfunction "VDDIO_4_80") (pintype "power_in"))
      (node (ref "IC2") (pin "96") (pinfunction "VDDIO_5_96") (pintype "power_in"))
      (node (ref "IC4") (pin "8") (pinfunction "VDD_8") (pintype "power_in"))
      (node (ref "JPPWR") (pin "1") (pinfunction "1_1") (pintype "passive"))
      (node (ref "JPPWR") (pin "2") (pinfunction "2_2") (pintype "passive"))
      (node (ref "JPRF") (pin "1") (pinfunction "1_1") (pintype "passive"))
      (node (ref "PWM0") (pin "1") (pinfunction "1_1") (pintype "passive"))
      (node (ref "R1") (pin "1") (pinfunction "1_1") (pintype "passive"))
      (node (ref "R16") (pin "2") (pinfunction "2_2") (pintype "passive"))
      (node (ref "SPI0_0") (pin "1") (pinfunction "1_1") (pintype "passive"))
      (node (ref "SPI0_1") (pin "1") (pinfunction "1_1") (pintype "passive"))
      (node (ref "SPI0_2") (pin "1") (pinfunction "1_1") (pintype "passive"))
      (node (ref "SPI0_3") (pin "1") (pinfunction "1_1") (pintype "passive"))
      (node (ref "SWITCH_SWD") (pin "3") (pinfunction "NC_1_3") (pintype "bidirectional"))
      (node (ref "UART") (pin "1") (pinfunction "1_1") (pintype "passive"))
      (node (ref "UART") (pin "2") (pinfunction "2_2") (pintype "passive"))
      (node (ref "USBALIM") (pin "2") (pinfunction "2_2") (pintype "passive"))
    )
    (net (code "120") (name "/VREFP") (class "Default")
      (node (ref "DAC") (pin "6") (pinfunction "6_6") (pintype "passive"))
      (node (ref "IC2") (pin "9") (pinfunction "VREFP_9") (pintype "input"))
      (node (ref "R15") (pin "2") (pinfunction "2_2") (pintype "passive"))
    )
    (net (code "121") (name "GND") (class "Default")
      (node (ref "ADC") (pin "3") (pinfunction "3_3") (pintype "passive"))
      (node (ref "ADC") (pin "4") (pinfunction "4_4") (pintype "passive"))
      (node (ref "C10") (pin "2") (pinfunction "2_2") (pintype "passive"))
      (node (ref "C11") (pin "2") (pinfunction "2_2") (pintype "passive"))
      (node (ref "C12") (pin "2") (pinfunction "2_2") (pintype "passive"))
      (node (ref "C13") (pin "1") (pinfunction "1_1") (pintype "passive"))
      (node (ref "C14") (pin "1") (pinfunction "1_1") (pintype "passive"))
      (node (ref "C15") (pin "1") (pinfunction "1_1") (pintype "passive"))
      (node (ref "C16") (pin "2") (pinfunction "2_2") (pintype "passive"))
      (node (ref "C17") (pin "2") (pinfunction "2_2") (pintype "passive"))
      (node (ref "C2") (pin "2") (pinfunction "2_2") (pintype "passive"))
      (node (ref "C20") (pin "2") (pinfunction "2_2") (pintype "passive"))
      (node (ref "C21") (pin "1") (pinfunction "1_1") (pintype "passive"))
      (node (ref "C22") (pin "2") (pinfunction "2_2") (pintype "passive"))
      (node (ref "C23") (pin "2") (pinfunction "2_2") (pintype "passive"))
      (node (ref "C24") (pin "2") (pinfunction "2_2") (pintype "passive"))
      (node (ref "C25") (pin "2") (pinfunction "2_2") (pintype "passive"))
      (node (ref "C26") (pin "2") (pinfunction "2_2") (pintype "passive"))
      (node (ref "C27") (pin "2") (pinfunction "2_2") (pintype "passive"))
      (node (ref "C3") (pin "2") (pinfunction "2_2") (pintype "passive"))
      (node (ref "C4") (pin "2") (pinfunction "2_2") (pintype "passive"))
      (node (ref "C6") (pin "2") (pinfunction "2_2") (pintype "passive"))
      (node (ref "C7") (pin "2") (pinfunction "2_2") (pintype "passive"))
      (node (ref "C8") (pin "2") (pinfunction "2_2") (pintype "passive"))
      (node (ref "C9") (pin "2") (pinfunction "2_2") (pintype "passive"))
      (node (ref "CC2500") (pin "1") (pinfunction "1_1") (pintype "bidirectional"))
      (node (ref "CC2500") (pin "19") (pinfunction "19_19") (pintype "bidirectional"))
      (node (ref "CC2500") (pin "22") (pinfunction "22_22") (pintype "bidirectional"))
      (node (ref "DAC") (pin "2") (pinfunction "2_2") (pintype "passive"))
      (node (ref "DBG_ON") (pin "C") (pinfunction "C_C") (pintype "passive"))
      (node (ref "FL1") (pin "2") (pinfunction "GND_2") (pintype "bidirectional"))
      (node (ref "FL2") (pin "2") (pinfunction "GND_2") (pintype "bidirectional"))
      (node (ref "IC1") (pin "12") (pinfunction "VSS_1_12") (pintype "bidirectional"))
      (node (ref "IC1") (pin "34") (pinfunction "VSS_2_34") (pintype "bidirectional"))
      (node (ref "IC2") (pin "104") (pinfunction "JTAGSEL_104") (pintype "input"))
      (node (ref "IC2") (pin "115") (pinfunction "GND_4_115") (pintype "power_in"))
      (node (ref "IC2") (pin "135") (pinfunction "GND_5_135") (pintype "power_in"))
      (node (ref "IC2") (pin "138") (pinfunction "GND_6_138") (pintype "power_in"))
      (node (ref "IC2") (pin "44") (pinfunction "GND_1_44") (pintype "power_in"))
      (node (ref "IC2") (pin "61") (pinfunction "GND_2_61") (pintype "power_in"))
      (node (ref "IC2") (pin "8") (pinfunction "VREFN_8") (pintype "input"))
      (node (ref "IC2") (pin "95") (pinfunction "GND_3_95") (pintype "power_in"))
      (node (ref "IC4") (pin "7") (pinfunction "GND_7") (pintype "power_in"))
      (node (ref "JP1") (pin "2") (pinfunction "2_2") (pintype "passive"))
      (node (ref "JPPWR") (pin "5") (pinfunction "5_5") (pintype "passive"))
      (node (ref "JPPWR") (pin "6") (pinfunction "6_6") (pintype "passive"))
      (node (ref "LED0") (pin "C") (pinfunction "C_C") (pintype "passive"))
      (node (ref "LED1") (pin "C") (pinfunction "C_C") (pintype "passive"))
      (node (ref "LED2") (pin "C") (pinfunction "C_C") (pintype "passive"))
      (node (ref "LED3") (pin "C") (pinfunction "C_C") (pintype "passive"))
      (node (ref "LED4") (pin "C") (pinfunction "C_C") (pintype "passive"))
      (node (ref "LED5") (pin "C") (pinfunction "C_C") (pintype "passive"))
      (node (ref "LED6") (pin "C") (pinfunction "C_C") (pintype "passive"))
      (node (ref "LED7") (pin "C") (pinfunction "C_C") (pintype "passive"))
      (node (ref "LED_2.2") (pin "C") (pinfunction "C_C") (pintype "passive"))
      (node (ref "LED_VAR") (pin "C") (pinfunction "C_C") (pintype "passive"))
      (node (ref "PWM0") (pin "2") (pinfunction "2_2") (pintype "passive"))
      (node (ref "R18") (pin "2") (pinfunction "2_2") (pintype "passive"))
      (node (ref "R21") (pin "1") (pinfunction "CCW_1") (pintype "bidirectional"))
      (node (ref "SPI0_0") (pin "2") (pinfunction "2_2") (pintype "passive"))
      (node (ref "SPI0_1") (pin "2") (pinfunction "2_2") (pintype "passive"))
      (node (ref "SPI0_2") (pin "2") (pinfunction "2_2") (pintype "passive"))
      (node (ref "SPI0_3") (pin "2") (pinfunction "2_2") (pintype "passive"))
      (node (ref "SWD") (pin "3") (pinfunction "3_3") (pintype "passive"))
      (node (ref "SWD") (pin "5") (pinfunction "5_5") (pintype "passive"))
      (node (ref "SWD") (pin "9") (pinfunction "9_9") (pintype "passive"))
      (node (ref "SWITCH_SWD") (pin "1") (pinfunction "NO_1_1") (pintype "bidirectional"))
      (node (ref "U$1") (pin "2") (pinfunction "P$3_2") (pintype "bidirectional"))
      (node (ref "UART") (pin "3") (pinfunction "3_3") (pintype "passive"))
      (node (ref "UART") (pin "4") (pinfunction "4_4") (pintype "passive"))
      (node (ref "USB-ALIM") (pin "5") (pinfunction "5_5") (pintype "bidirectional"))
    )
    (net (code "122") (name "Net-(DBG_ON-PadA)") (class "Default")
      (node (ref "DBG_ON") (pin "A") (pinfunction "A_A") (pintype "passive"))
      (node (ref "R14") (pin "1") (pinfunction "1_1") (pintype "passive"))
    )
    (net (code "123") (name "Net-(FL1-ADJ)") (class "Default")
      (node (ref "C22") (pin "1") (pinfunction "1_1") (pintype "passive"))
      (node (ref "FL1") (pin "4") (pinfunction "ADJ_4") (pintype "bidirectional"))
      (node (ref "R17") (pin "2") (pinfunction "2_2") (pintype "passive"))
      (node (ref "R18") (pin "1") (pinfunction "1_1") (pintype "passive"))
    )
    (net (code "124") (name "Net-(FL2-ADJ)") (class "Default")
      (node (ref "C24") (pin "1") (pinfunction "1_1") (pintype "passive"))
      (node (ref "FL2") (pin "4") (pinfunction "ADJ_4") (pintype "bidirectional"))
      (node (ref "R19") (pin "2") (pinfunction "2_2") (pintype "passive"))
      (node (ref "R20") (pin "1") (pinfunction "1_1") (pintype "passive"))
    )
    (net (code "125") (name "Net-(IC2-VDDPLL)") (class "Default")
      (node (ref "C17") (pin "1") (pinfunction "1_1") (pintype "passive"))
      (node (ref "IC2") (pin "123") (pinfunction "VDDPLL_123") (pintype "power_in"))
      (node (ref "R3") (pin "2") (pinfunction "2_2") (pintype "passive"))
    )
    (net (code "126") (name "Net-(IC2-VDDPLLUSB)") (class "Default")
      (node (ref "C15") (pin "2") (pinfunction "2_2") (pintype "passive"))
      (node (ref "IC2") (pin "143") (pinfunction "VDDPLLUSB_143") (pintype "power_in"))
      (node (ref "L1") (pin "2") (pinfunction "2_2") (pintype "passive"))
    )
    (net (code "127") (name "Net-(IC2-VDDUTMIC)") (class "Default")
      (node (ref "C16") (pin "1") (pinfunction "1_1") (pintype "passive"))
      (node (ref "IC2") (pin "139") (pinfunction "VDDUTMIC_139") (pintype "power_in"))
      (node (ref "R2") (pin "2") (pinfunction "2_2") (pintype "passive"))
    )
    (net (code "128") (name "Net-(L1-Pad1)") (class "Default")
      (node (ref "L1") (pin "1") (pinfunction "1_1") (pintype "passive"))
      (node (ref "R1") (pin "2") (pinfunction "2_2") (pintype "passive"))
    )
    (net (code "129") (name "Net-(LED0-PadA)") (class "Default")
      (node (ref "LED0") (pin "A") (pinfunction "A_A") (pintype "passive"))
      (node (ref "R6") (pin "1") (pinfunction "1_1") (pintype "passive"))
    )
    (net (code "130") (name "Net-(LED1-PadA)") (class "Default")
      (node (ref "LED1") (pin "A") (pinfunction "A_A") (pintype "passive"))
      (node (ref "R7") (pin "1") (pinfunction "1_1") (pintype "passive"))
    )
    (net (code "131") (name "Net-(LED2-PadA)") (class "Default")
      (node (ref "LED2") (pin "A") (pinfunction "A_A") (pintype "passive"))
      (node (ref "R8") (pin "1") (pinfunction "1_1") (pintype "passive"))
    )
    (net (code "132") (name "Net-(LED3-PadA)") (class "Default")
      (node (ref "LED3") (pin "A") (pinfunction "A_A") (pintype "passive"))
      (node (ref "R9") (pin "1") (pinfunction "1_1") (pintype "passive"))
    )
    (net (code "133") (name "Net-(LED4-PadA)") (class "Default")
      (node (ref "LED4") (pin "A") (pinfunction "A_A") (pintype "passive"))
      (node (ref "R10") (pin "1") (pinfunction "1_1") (pintype "passive"))
    )
    (net (code "134") (name "Net-(LED5-PadA)") (class "Default")
      (node (ref "LED5") (pin "A") (pinfunction "A_A") (pintype "passive"))
      (node (ref "R11") (pin "1") (pinfunction "1_1") (pintype "passive"))
    )
    (net (code "135") (name "Net-(LED6-PadA)") (class "Default")
      (node (ref "LED6") (pin "A") (pinfunction "A_A") (pintype "passive"))
      (node (ref "R12") (pin "1") (pinfunction "1_1") (pintype "passive"))
    )
    (net (code "136") (name "Net-(LED7-PadA)") (class "Default")
      (node (ref "LED7") (pin "A") (pinfunction "A_A") (pintype "passive"))
      (node (ref "R13") (pin "1") (pinfunction "1_1") (pintype "passive"))
    )
    (net (code "137") (name "Net-(R20-Pad2)") (class "Default")
      (node (ref "R20") (pin "2") (pinfunction "2_2") (pintype "passive"))
      (node (ref "R21") (pin "2") (pinfunction "2_2") (pintype "bidirectional"))
    )
    (net (code "138") (name "Net-(SWITCH_ALIM-COM_2)") (class "Default")
      (node (ref "R22") (pin "1") (pinfunction "1_1") (pintype "passive"))
      (node (ref "SWITCH_ALIM") (pin "5") (pinfunction "COM_2_5") (pintype "bidirectional"))
    )
    (net (code "139") (name "Net-(SWITCH_ALIM-NC_2)") (class "Default")
      (node (ref "LED_2.2") (pin "A") (pinfunction "A_A") (pintype "passive"))
      (node (ref "SWITCH_ALIM") (pin "6") (pinfunction "NC_2_6") (pintype "bidirectional"))
    )
    (net (code "140") (name "Net-(SWITCH_ALIM-NO_2)") (class "Default")
      (node (ref "LED_VAR") (pin "A") (pinfunction "A_A") (pintype "passive"))
      (node (ref "SWITCH_ALIM") (pin "4") (pinfunction "NO_2_4") (pintype "bidirectional"))
    )
    (net (code "141") (name "unconnected-(CC2500-Pad2)") (class "Default")
      (node (ref "CC2500") (pin "2") (pinfunction "2_2") (pintype "bidirectional"))
    )
    (net (code "142") (name "unconnected-(CC2500-Pad3)") (class "Default")
      (node (ref "CC2500") (pin "3") (pinfunction "3_3") (pintype "bidirectional"))
    )
    (net (code "143") (name "unconnected-(CC2500-Pad4)") (class "Default")
      (node (ref "CC2500") (pin "4") (pinfunction "4_4") (pintype "bidirectional"))
    )
    (net (code "144") (name "unconnected-(CC2500-Pad5)") (class "Default")
      (node (ref "CC2500") (pin "5") (pinfunction "5_5") (pintype "bidirectional"))
    )
    (net (code "145") (name "unconnected-(CC2500-Pad6)") (class "Default")
      (node (ref "CC2500") (pin "6") (pinfunction "6_6") (pintype "bidirectional"))
    )
    (net (code "146") (name "unconnected-(CC2500-Pad7)") (class "Default")
      (node (ref "CC2500") (pin "7") (pinfunction "7_7") (pintype "bidirectional"))
    )
    (net (code "147") (name "unconnected-(CC2500-Pad8)") (class "Default")
      (node (ref "CC2500") (pin "8") (pinfunction "8_8") (pintype "bidirectional"))
    )
    (net (code "148") (name "unconnected-(CC2500-Pad9)") (class "Default")
      (node (ref "CC2500") (pin "9") (pinfunction "9_9") (pintype "bidirectional"))
    )
    (net (code "149") (name "unconnected-(CC2500-Pad11)") (class "Default")
      (node (ref "CC2500") (pin "11") (pinfunction "11_11") (pintype "bidirectional"))
    )
    (net (code "150") (name "unconnected-(CC2500-Pad13)") (class "Default")
      (node (ref "CC2500") (pin "13") (pinfunction "13_13") (pintype "bidirectional"))
    )
    (net (code "151") (name "unconnected-(CC2500-Pad15)") (class "Default")
      (node (ref "CC2500") (pin "15") (pinfunction "15_15") (pintype "bidirectional"))
    )
    (net (code "152") (name "unconnected-(CC2500-Pad17)") (class "Default")
      (node (ref "CC2500") (pin "17") (pinfunction "17_17") (pintype "bidirectional"))
    )
    (net (code "153") (name "unconnected-(CC2500-Pad21)") (class "Default")
      (node (ref "CC2500") (pin "21") (pinfunction "21_21") (pintype "bidirectional"))
    )
    (net (code "154") (name "unconnected-(CC2500-Pad23)") (class "Default")
      (node (ref "CC2500") (pin "23") (pinfunction "23_23") (pintype "bidirectional"))
    )
    (net (code "155") (name "unconnected-(CC2500-Pad24)") (class "Default")
      (node (ref "CC2500") (pin "24") (pinfunction "24_24") (pintype "bidirectional"))
    )
    (net (code "156") (name "unconnected-(CC2500-Pad25)") (class "Default")
      (node (ref "CC2500") (pin "25") (pinfunction "25_25") (pintype "bidirectional"))
    )
    (net (code "157") (name "unconnected-(CC2500-Pad26)") (class "Default")
      (node (ref "CC2500") (pin "26") (pinfunction "26_26") (pintype "bidirectional"))
    )
    (net (code "158") (name "unconnected-(CC2500-Pad28)") (class "Default")
      (node (ref "CC2500") (pin "28") (pinfunction "28_28") (pintype "bidirectional"))
    )
    (net (code "159") (name "unconnected-(CC2500-Pad30)") (class "Default")
      (node (ref "CC2500") (pin "30") (pinfunction "30_30") (pintype "bidirectional"))
    )
    (net (code "160") (name "unconnected-(CC2500-Pad31)") (class "Default")
      (node (ref "CC2500") (pin "31") (pinfunction "31_31") (pintype "bidirectional"))
    )
    (net (code "161") (name "unconnected-(CC2500-Pad32)") (class "Default")
      (node (ref "CC2500") (pin "32") (pinfunction "32_32") (pintype "bidirectional"))
    )
    (net (code "162") (name "unconnected-(CC2500-Pad33)") (class "Default")
      (node (ref "CC2500") (pin "33") (pinfunction "33_33") (pintype "bidirectional"))
    )
    (net (code "163") (name "unconnected-(CC2500-Pad34)") (class "Default")
      (node (ref "CC2500") (pin "34") (pinfunction "34_34") (pintype "bidirectional"))
    )
    (net (code "164") (name "unconnected-(CC2500-Pad35)") (class "Default")
      (node (ref "CC2500") (pin "35") (pinfunction "35_35") (pintype "bidirectional"))
    )
    (net (code "165") (name "unconnected-(CC2500-Pad36)") (class "Default")
      (node (ref "CC2500") (pin "36") (pinfunction "36_36") (pintype "bidirectional"))
    )
    (net (code "166") (name "unconnected-(CC2500-Pad37)") (class "Default")
      (node (ref "CC2500") (pin "37") (pinfunction "37_37") (pintype "bidirectional"))
    )
    (net (code "167") (name "unconnected-(CC2500-Pad38)") (class "Default")
      (node (ref "CC2500") (pin "38") (pinfunction "38_38") (pintype "bidirectional"))
    )
    (net (code "168") (name "unconnected-(CC2500-Pad39)") (class "Default")
      (node (ref "CC2500") (pin "39") (pinfunction "39_39") (pintype "bidirectional"))
    )
    (net (code "169") (name "unconnected-(CC2500-Pad40)") (class "Default")
      (node (ref "CC2500") (pin "40") (pinfunction "40_40") (pintype "bidirectional"))
    )
    (net (code "170") (name "unconnected-(GPIO_BOTTOM-Pad14)") (class "Default")
      (node (ref "GPIO_BOTTOM") (pin "14") (pinfunction "14_14") (pintype "passive"))
    )
    (net (code "171") (name "unconnected-(IC2-HSDM_1-Pad136)") (class "Default")
      (node (ref "IC2") (pin "136") (pinfunction "HSDM_1_136") (pintype "bidirectional"))
    )
    (net (code "172") (name "unconnected-(IC2-HSDM_2-Pad137)") (class "Default")
      (node (ref "IC2") (pin "137") (pinfunction "HSDM_2_137") (pintype "bidirectional"))
    )
    (net (code "173") (name "unconnected-(IC2-PA7-Pad35)") (class "Default")
      (node (ref "IC2") (pin "35") (pinfunction "PA7_35") (pintype "bidirectional"))
    )
    (net (code "174") (name "unconnected-(IC2-PB8-Pad141)") (class "Default")
      (node (ref "IC2") (pin "141") (pinfunction "PB8_141") (pintype "bidirectional"))
    )
    (net (code "175") (name "unconnected-(IC2-PB9-Pad142)") (class "Default")
      (node (ref "IC2") (pin "142") (pinfunction "PB9_142") (pintype "bidirectional"))
    )
    (net (code "176") (name "unconnected-(IC2-PC17-Pad103)") (class "Default")
      (node (ref "IC2") (pin "103") (pinfunction "PC17_103") (pintype "bidirectional"))
    )
    (net (code "177") (name "unconnected-(IC2-TST-Pad85)") (class "Default")
      (node (ref "IC2") (pin "85") (pinfunction "TST_85") (pintype "input"))
    )
    (net (code "178") (name "unconnected-(IC2-VBG-Pad140)") (class "Default")
      (node (ref "IC2") (pin "140") (pinfunction "VBG_140") (pintype "input"))
    )
    (net (code "179") (name "unconnected-(IC4-CT-Pad6)") (class "Default")
      (node (ref "IC4") (pin "6") (pinfunction "CT_6") (pintype "bidirectional"))
    )
    (net (code "180") (name "unconnected-(IC4-INT-Pad5)") (class "Default")
      (node (ref "IC4") (pin "5") (pinfunction "INT_5") (pintype "input"))
    )
    (net (code "181") (name "unconnected-(R21-CW-Pad3)") (class "Default")
      (node (ref "R21") (pin "3") (pinfunction "CW_3") (pintype "bidirectional"))
    )
    (net (code "182") (name "unconnected-(SWD-Pad7)") (class "Default")
      (node (ref "SWD") (pin "7") (pinfunction "7_7") (pintype "passive"))
    )
    (net (code "183") (name "unconnected-(SWD-Pad8)") (class "Default")
      (node (ref "SWD") (pin "8") (pinfunction "8_8") (pintype "passive"))
    )
    (net (code "184") (name "unconnected-(SWITCH_ALIM-PadMH1)") (class "Default")
      (node (ref "SWITCH_ALIM") (pin "MH1") (pinfunction "MH1_MH1") (pintype "bidirectional"))
    )
    (net (code "185") (name "unconnected-(SWITCH_ALIM-PadMH2)") (class "Default")
      (node (ref "SWITCH_ALIM") (pin "MH2") (pinfunction "MH2_MH2") (pintype "bidirectional"))
    )
    (net (code "186") (name "unconnected-(SWITCH_SWD-COM_2-Pad5)") (class "Default")
      (node (ref "SWITCH_SWD") (pin "5") (pinfunction "COM_2_5") (pintype "bidirectional"))
    )
    (net (code "187") (name "unconnected-(SWITCH_SWD-NC_2-Pad6)") (class "Default")
      (node (ref "SWITCH_SWD") (pin "6") (pinfunction "NC_2_6") (pintype "bidirectional"))
    )
    (net (code "188") (name "unconnected-(SWITCH_SWD-NO_2-Pad4)") (class "Default")
      (node (ref "SWITCH_SWD") (pin "4") (pinfunction "NO_2_4") (pintype "bidirectional"))
    )
    (net (code "189") (name "unconnected-(SWITCH_SWD-PadMH1)") (class "Default")
      (node (ref "SWITCH_SWD") (pin "MH1") (pinfunction "MH1_MH1") (pintype "bidirectional"))
    )
    (net (code "190") (name "unconnected-(SWITCH_SWD-PadMH2)") (class "Default")
      (node (ref "SWITCH_SWD") (pin "MH2") (pinfunction "MH2_MH2") (pintype "bidirectional"))
    )
    (net (code "191") (name "unconnected-(USB-ALIM-Pad2)") (class "Default")
      (node (ref "USB-ALIM") (pin "2") (pinfunction "2_2") (pintype "bidirectional"))
    )
    (net (code "192") (name "unconnected-(USB-ALIM-Pad3)") (class "Default")
      (node (ref "USB-ALIM") (pin "3") (pinfunction "3_3") (pintype "bidirectional"))
    )
    (net (code "193") (name "unconnected-(USB-ALIM-Pad4)") (class "Default")
      (node (ref "USB-ALIM") (pin "4") (pinfunction "4_4") (pintype "bidirectional"))
    )
    (net (code "194") (name "unconnected-(USB-ALIM-PadMH1)") (class "Default")
      (node (ref "USB-ALIM") (pin "MH1") (pinfunction "MH1_MH1") (pintype "bidirectional"))
    )
    (net (code "195") (name "unconnected-(USB-ALIM-PadMH2)") (class "Default")
      (node (ref "USB-ALIM") (pin "MH2") (pinfunction "MH2_MH2") (pintype "bidirectional"))
    )
    (net (code "196") (name "unconnected-(USB-ALIM-PadMP1)") (class "Default")
      (node (ref "USB-ALIM") (pin "MP1") (pinfunction "MP1_MP1") (pintype "bidirectional"))
    )
    (net (code "197") (name "unconnected-(USB-ALIM-PadMP2)") (class "Default")
      (node (ref "USB-ALIM") (pin "MP2") (pinfunction "MP2_MP2") (pintype "bidirectional"))
    )
    (net (code "198") (name "unconnected-(USB-ALIM-PadMP3)") (class "Default")
      (node (ref "USB-ALIM") (pin "MP3") (pinfunction "MP3_MP3") (pintype "bidirectional"))
    )
    (net (code "199") (name "unconnected-(USB-ALIM-PadMP4)") (class "Default")
      (node (ref "USB-ALIM") (pin "MP4") (pinfunction "MP4_MP4") (pintype "bidirectional"))
    )
  )
)
